# mySensorsRS485GW_back.net
KiCad netlist of a schematic drawn in EAGLE
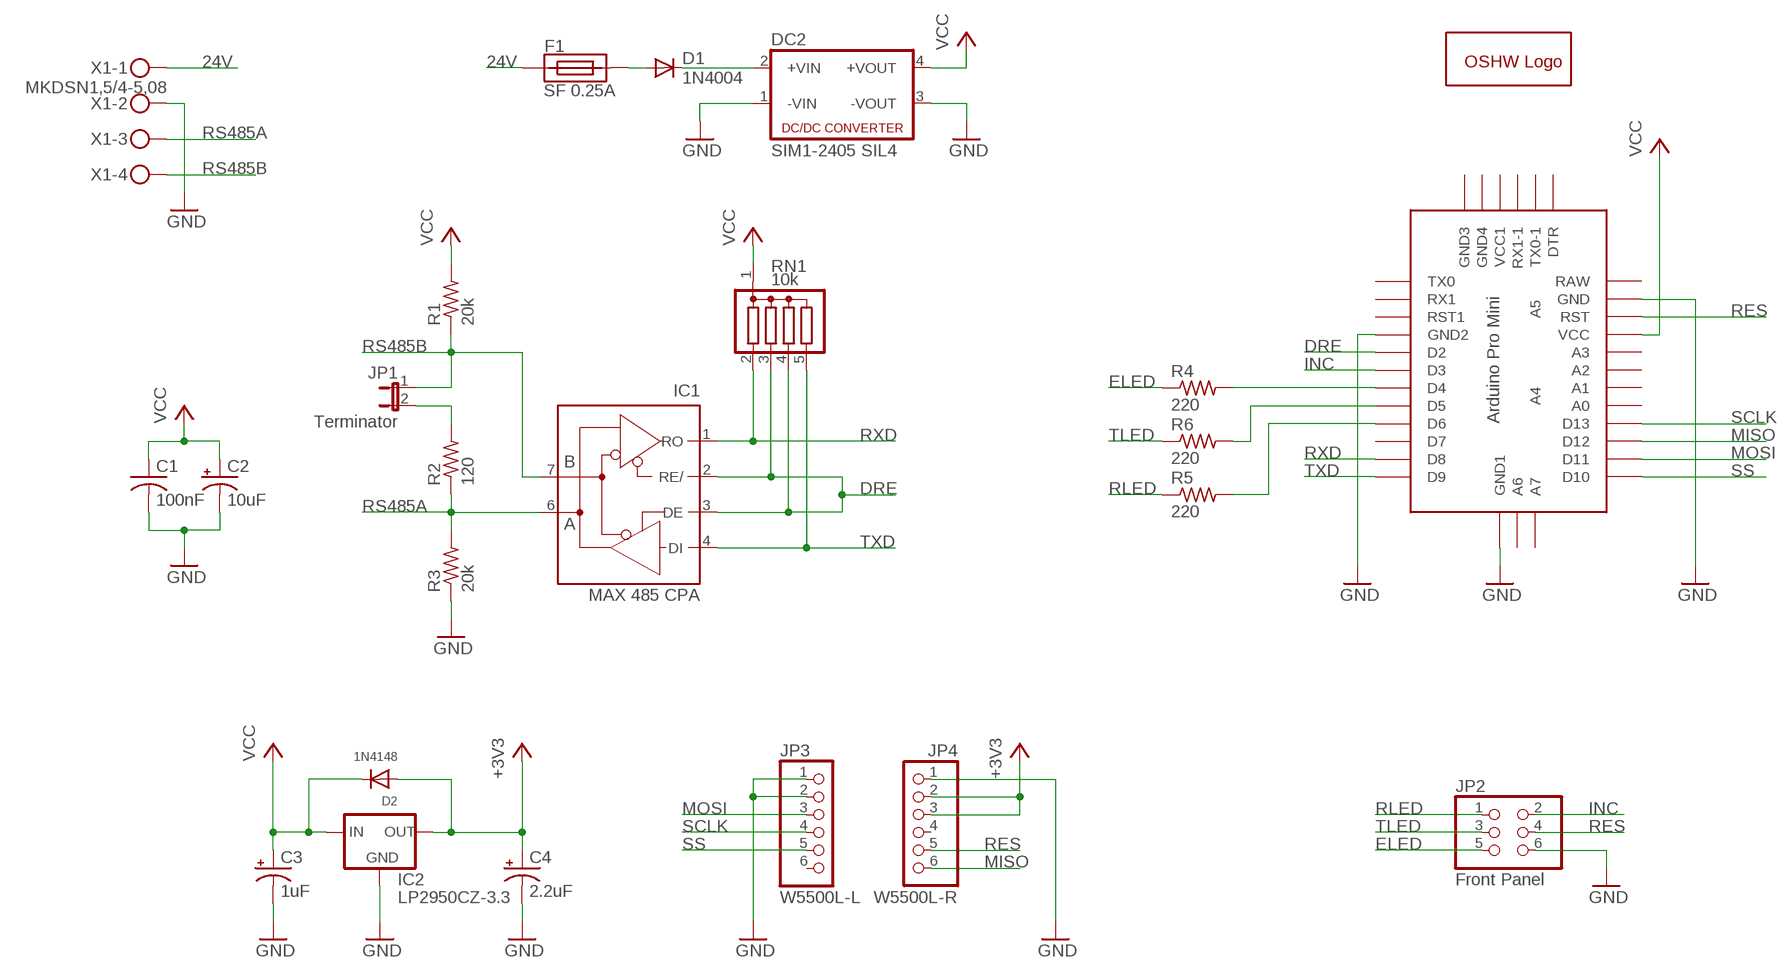
[diagram p0: schematic, sheet 1]

(export (version "E")
  (design (tool "Eeschema 10.0.6"))
  (components
    (comp (ref "C1")
      (value "100nF")
      (footprint "eagle-import:C025-025X050")
      (libsource (lib "eagle-import") (part "C-US025-025X050"))
    )
    (comp (ref "C2")
      (value "10uF")
      (footprint "eagle-import:TT2D5")
      (libsource (lib "eagle-import") (part "CPOL-USTT2D5"))
    )
    (comp (ref "C3")
      (value "1uF")
      (footprint "eagle-import:TT2D5")
      (libsource (lib "eagle-import") (part "CPOL-USTT2D5"))
    )
    (comp (ref "C4")
      (value "2.2uF")
      (footprint "eagle-import:TT2D5")
      (libsource (lib "eagle-import") (part "CPOL-USTT2D5"))
    )
    (comp (ref "D1")
      (value "1N4004")
      (footprint "eagle-import:DO41-10")
      (libsource (lib "eagle-import") (part "1N4004"))
    )
    (comp (ref "D2")
      (value "1N4148")
      (footprint "eagle-import:DO-1N4148")
      (libsource (lib "eagle-import") (part "DIODEDO-1N4148"))
    )
    (comp (ref "DC2")
      (value "SIM1-2405 SIL4")
      (footprint "eagle-import:NME")
      (fields (field (name "MF") "C & D TECHNOLOGIES, INC") (field (name "MPN") "NME1205D"))
      (libsource (lib "eagle-import") (part "NME"))
    )
    (comp (ref "F1")
      (value "SF 0.25A")
      (footprint "eagle-import:NANO2_SMF_FUSEBLOCK")
      (libsource (lib "eagle-import") (part "SMF_OMNIBLOK_154.062"))
    )
    (comp (ref "GOLD_ORB_SM1")
      (value "OSHWLOGOLOGO5MM")
      (footprint "eagle-import:OSHW_5MM")
      (libsource (lib "eagle-import") (part "OSHWLOGOLOGO5MM"))
    )
    (comp (ref "IC1")
      (value "MAX 485 CPA")
      (footprint "eagle-import:DIL08")
      (fields (field (name "MPN") "MAX481CPA+"))
      (libsource (lib "eagle-import") (part "MAX481CPA"))
    )
    (comp (ref "IC2")
      (value "LP2950CZ-3.3")
      (footprint "eagle-import:TO92")
      (libsource (lib "eagle-import") (part "LP2950?CZ-3.3"))
    )
    (comp (ref "JP1")
      (value "Terminator")
      (footprint "eagle-import:JP1")
      (libsource (lib "eagle-import") (part "JP1E"))
    )
    (comp (ref "JP2")
      (value "Front Panel")
      (footprint "eagle-import:2X03")
      (libsource (lib "eagle-import") (part "PINHD-2X3"))
    )
    (comp (ref "JP3")
      (value "W5500L-L")
      (footprint "eagle-import:1X06")
      (libsource (lib "eagle-import") (part "PINHD-1X6"))
    )
    (comp (ref "JP4")
      (value "W5500L-R")
      (footprint "eagle-import:1X06")
      (libsource (lib "eagle-import") (part "PINHD-1X6"))
    )
    (comp (ref "R1")
      (value "20k")
      (footprint "eagle-import:0207_2V")
      (libsource (lib "eagle-import") (part "R-US_0207/2V"))
    )
    (comp (ref "R2")
      (value "120")
      (footprint "eagle-import:0207_2V")
      (libsource (lib "eagle-import") (part "R-US_0207/2V"))
    )
    (comp (ref "R3")
      (value "20k")
      (footprint "eagle-import:0207_2V")
      (libsource (lib "eagle-import") (part "R-US_0207/2V"))
    )
    (comp (ref "R4")
      (value "220")
      (footprint "eagle-import:0207_7")
      (libsource (lib "eagle-import") (part "R-US_0207/7"))
    )
    (comp (ref "R5")
      (value "220")
      (footprint "eagle-import:0207_7")
      (libsource (lib "eagle-import") (part "R-US_0207/7"))
    )
    (comp (ref "R6")
      (value "220")
      (footprint "eagle-import:0207_7")
      (libsource (lib "eagle-import") (part "R-US_0207/7"))
    )
    (comp (ref "RN1")
      (value "10k")
      (footprint "eagle-import:SIL5")
      (libsource (lib "eagle-import") (part "G04R"))
    )
    (comp (ref "U$1")
      (value "ABK-PRO-MINI")
      (footprint "eagle-import:ABK-PRO-MINI")
      (libsource (lib "eagle-import") (part "ABK-PRO-MINI"))
    )
    (comp (ref "X1")
      (value "MKDSN1,5/4-5,08")
      (footprint "eagle-import:MKDSN1,5_4-5,08")
      (libsource (lib "eagle-import") (part "MKDSN1,5/4-5,08"))
    )
  )
  (nets
    (net (code "1") (name "+3V3") (class "Default")
      (node (ref "C4") (pin "+") (pinfunction "+_+") (pintype "passive"))
      (node (ref "D2") (pin "A") (pinfunction "A_A") (pintype "passive"))
      (node (ref "IC2") (pin "1") (pinfunction "OUT_1") (pintype "passive"))
      (node (ref "JP4") (pin "2") (pinfunction "2_2") (pintype "passive"))
      (node (ref "JP4") (pin "3") (pinfunction "3_3") (pintype "passive"))
    )
    (net (code "2") (name "/24V") (class "Default")
      (node (ref "F1") (pin "1") (pinfunction "1_1") (pintype "passive"))
      (node (ref "X1") (pin "1") (pinfunction "KL_1") (pintype "passive"))
    )
    (net (code "3") (name "/DRE") (class "Default")
      (node (ref "IC1") (pin "2") (pinfunction "RE/_2") (pintype "input"))
      (node (ref "IC1") (pin "3") (pinfunction "DE_3") (pintype "input"))
      (node (ref "RN1") (pin "3") (pinfunction "3_3") (pintype "passive"))
      (node (ref "RN1") (pin "4") (pinfunction "4_4") (pintype "passive"))
      (node (ref "U$1") (pin "D2") (pinfunction "D2_D2") (pintype "bidirectional"))
    )
    (net (code "4") (name "/ELED") (class "Default")
      (node (ref "JP2") (pin "5") (pinfunction "5_5") (pintype "passive"))
      (node (ref "R4") (pin "1") (pinfunction "1_1") (pintype "passive"))
    )
    (net (code "5") (name "/INC") (class "Default")
      (node (ref "JP2") (pin "2") (pinfunction "2_2") (pintype "passive"))
      (node (ref "U$1") (pin "D3") (pinfunction "D3_D3") (pintype "bidirectional"))
    )
    (net (code "6") (name "/MISO") (class "Default")
      (node (ref "JP4") (pin "6") (pinfunction "6_6") (pintype "passive"))
      (node (ref "U$1") (pin "D12") (pinfunction "D12_D12") (pintype "bidirectional"))
    )
    (net (code "7") (name "/MOSI") (class "Default")
      (node (ref "JP3") (pin "3") (pinfunction "3_3") (pintype "passive"))
      (node (ref "U$1") (pin "D11") (pinfunction "D11_D11") (pintype "bidirectional"))
    )
    (net (code "8") (name "/RES") (class "Default")
      (node (ref "JP2") (pin "4") (pinfunction "4_4") (pintype "passive"))
      (node (ref "JP4") (pin "5") (pinfunction "5_5") (pintype "passive"))
      (node (ref "U$1") (pin "RST") (pinfunction "RST_RST") (pintype "bidirectional"))
    )
    (net (code "9") (name "/RLED") (class "Default")
      (node (ref "JP2") (pin "1") (pinfunction "1_1") (pintype "passive"))
      (node (ref "R5") (pin "1") (pinfunction "1_1") (pintype "passive"))
    )
    (net (code "10") (name "/RS485A") (class "Default")
      (node (ref "IC1") (pin "6") (pinfunction "A_6") (pintype "passive"))
      (node (ref "R2") (pin "1") (pinfunction "1_1") (pintype "passive"))
      (node (ref "R3") (pin "2") (pinfunction "2_2") (pintype "passive"))
      (node (ref "X1") (pin "3") (pinfunction "KL_3") (pintype "passive"))
    )
    (net (code "11") (name "/RS485B") (class "Default")
      (node (ref "IC1") (pin "7") (pinfunction "B_7") (pintype "passive"))
      (node (ref "JP1") (pin "1") (pinfunction "1_1") (pintype "passive"))
      (node (ref "R1") (pin "1") (pinfunction "1_1") (pintype "passive"))
      (node (ref "X1") (pin "4") (pinfunction "KL_4") (pintype "passive"))
    )
    (net (code "12") (name "/RXD") (class "Default")
      (node (ref "IC1") (pin "1") (pinfunction "RO_1") (pintype "output"))
      (node (ref "RN1") (pin "2") (pinfunction "2_2") (pintype "passive"))
      (node (ref "U$1") (pin "D8") (pinfunction "D8_D8") (pintype "bidirectional"))
    )
    (net (code "13") (name "/SCLK") (class "Default")
      (node (ref "JP3") (pin "4") (pinfunction "4_4") (pintype "passive"))
      (node (ref "U$1") (pin "D13") (pinfunction "D13_D13") (pintype "bidirectional"))
    )
    (net (code "14") (name "/SS") (class "Default")
      (node (ref "JP3") (pin "5") (pinfunction "5_5") (pintype "passive"))
      (node (ref "U$1") (pin "D10") (pinfunction "D10_D10") (pintype "bidirectional"))
    )
    (net (code "15") (name "/TLED") (class "Default")
      (node (ref "JP2") (pin "3") (pinfunction "3_3") (pintype "passive"))
      (node (ref "R6") (pin "1") (pinfunction "1_1") (pintype "passive"))
    )
    (net (code "16") (name "/TXD") (class "Default")
      (node (ref "IC1") (pin "4") (pinfunction "DI_4") (pintype "input"))
      (node (ref "RN1") (pin "5") (pinfunction "5_5") (pintype "passive"))
      (node (ref "U$1") (pin "D9") (pinfunction "D9_D9") (pintype "bidirectional"))
    )
    (net (code "17") (name "GND") (class "Default")
      (node (ref "C1") (pin "2") (pinfunction "2_2") (pintype "passive"))
      (node (ref "C2") (pin "-") (pinfunction "-_-") (pintype "passive"))
      (node (ref "C3") (pin "-") (pinfunction "-_-") (pintype "passive"))
      (node (ref "C4") (pin "-") (pinfunction "-_-") (pintype "passive"))
      (node (ref "DC2") (pin "1") (pinfunction "-VIN_1") (pintype "passive"))
      (node (ref "DC2") (pin "3") (pinfunction "-VOUT_3") (pintype "passive"))
      (node (ref "IC2") (pin "2") (pinfunction "GND_2") (pintype "input"))
      (node (ref "JP2") (pin "6") (pinfunction "6_6") (pintype "passive"))
      (node (ref "JP3") (pin "1") (pinfunction "1_1") (pintype "passive"))
      (node (ref "JP3") (pin "2") (pinfunction "2_2") (pintype "passive"))
      (node (ref "JP4") (pin "1") (pinfunction "1_1") (pintype "passive"))
      (node (ref "R3") (pin "1") (pinfunction "1_1") (pintype "passive"))
      (node (ref "U$1") (pin "GND") (pinfunction "GND_GND") (pintype "bidirectional"))
      (node (ref "U$1") (pin "GND1") (pinfunction "GND2_GND1") (pintype "bidirectional"))
      (node (ref "U$1") (pin "GND4") (pinfunction "GND1_GND4") (pintype "bidirectional"))
      (node (ref "X1") (pin "2") (pinfunction "KL_2") (pintype "passive"))
    )
    (net (code "18") (name "Net-(D1-PadA)") (class "Default")
      (node (ref "D1") (pin "A") (pinfunction "A_A") (pintype "passive"))
      (node (ref "F1") (pin "2") (pinfunction "2_2") (pintype "passive"))
    )
    (net (code "19") (name "Net-(DC2-+VIN)") (class "Default")
      (node (ref "D1") (pin "C") (pinfunction "C_C") (pintype "passive"))
      (node (ref "DC2") (pin "2") (pinfunction "+VIN_2") (pintype "passive"))
    )
    (net (code "20") (name "Net-(JP1-Pad2)") (class "Default")
      (node (ref "JP1") (pin "2") (pinfunction "2_2") (pintype "passive"))
      (node (ref "R2") (pin "2") (pinfunction "2_2") (pintype "passive"))
    )
    (net (code "21") (name "Net-(R4-Pad2)") (class "Default")
      (node (ref "R4") (pin "2") (pinfunction "2_2") (pintype "passive"))
      (node (ref "U$1") (pin "D4") (pinfunction "D4_D4") (pintype "bidirectional"))
    )
    (net (code "22") (name "Net-(R5-Pad2)") (class "Default")
      (node (ref "R5") (pin "2") (pinfunction "2_2") (pintype "passive"))
      (node (ref "U$1") (pin "D6") (pinfunction "D6_D6") (pintype "bidirectional"))
    )
    (net (code "23") (name "Net-(R6-Pad2)") (class "Default")
      (node (ref "R6") (pin "2") (pinfunction "2_2") (pintype "passive"))
      (node (ref "U$1") (pin "D5") (pinfunction "D5_D5") (pintype "bidirectional"))
    )
    (net (code "24") (name "VCC") (class "Default")
      (node (ref "C1") (pin "1") (pinfunction "1_1") (pintype "passive"))
      (node (ref "C2") (pin "+") (pinfunction "+_+") (pintype "passive"))
      (node (ref "C3") (pin "+") (pinfunction "+_+") (pintype "passive"))
      (node (ref "D2") (pin "C") (pinfunction "C_C") (pintype "passive"))
      (node (ref "DC2") (pin "4") (pinfunction "+VOUT_4") (pintype "passive"))
      (node (ref "IC2") (pin "3") (pinfunction "IN_3") (pintype "input"))
      (node (ref "R1") (pin "2") (pinfunction "2_2") (pintype "passive"))
      (node (ref "RN1") (pin "1") (pinfunction "1_1") (pintype "passive"))
      (node (ref "U$1") (pin "VCC") (pinfunction "VCC_VCC") (pintype "bidirectional"))
    )
    (net (code "25") (name "unconnected-(JP3-Pad6)") (class "Default")
      (node (ref "JP3") (pin "6") (pinfunction "6_6") (pintype "passive"))
    )
    (net (code "26") (name "unconnected-(JP4-Pad4)") (class "Default")
      (node (ref "JP4") (pin "4") (pinfunction "4_4") (pintype "passive"))
    )
    (net (code "27") (name "unconnected-(U$1-GND3-PadGND2)") (class "Default")
      (node (ref "U$1") (pin "GND2") (pinfunction "GND3_GND2") (pintype "bidirectional"))
    )
    (net (code "28") (name "unconnected-(U$1-GND4-PadGND3)") (class "Default")
      (node (ref "U$1") (pin "GND3") (pinfunction "GND4_GND3") (pintype "bidirectional"))
    )
    (net (code "29") (name "unconnected-(U$1-PadA0)") (class "Default")
      (node (ref "U$1") (pin "A0") (pinfunction "A0_A0") (pintype "bidirectional"))
    )
    (net (code "30") (name "unconnected-(U$1-PadA1)") (class "Default")
      (node (ref "U$1") (pin "A1") (pinfunction "A1_A1") (pintype "bidirectional"))
    )
    (net (code "31") (name "unconnected-(U$1-PadA2)") (class "Default")
      (node (ref "U$1") (pin "A2") (pinfunction "A2_A2") (pintype "bidirectional"))
    )
    (net (code "32") (name "unconnected-(U$1-PadA3)") (class "Default")
      (node (ref "U$1") (pin "A3") (pinfunction "A3_A3") (pintype "bidirectional"))
    )
    (net (code "33") (name "unconnected-(U$1-PadA4)") (class "Default")
      (node (ref "U$1") (pin "A4") (pinfunction "A4_A4") (pintype "bidirectional"))
    )
    (net (code "34") (name "unconnected-(U$1-PadA5)") (class "Default")
      (node (ref "U$1") (pin "A5") (pinfunction "A5_A5") (pintype "bidirectional"))
    )
    (net (code "35") (name "unconnected-(U$1-PadA6)") (class "Default")
      (node (ref "U$1") (pin "A6") (pinfunction "A6_A6") (pintype "bidirectional"))
    )
    (net (code "36") (name "unconnected-(U$1-PadA7)") (class "Default")
      (node (ref "U$1") (pin "A7") (pinfunction "A7_A7") (pintype "bidirectional"))
    )
    (net (code "37") (name "unconnected-(U$1-PadD7)") (class "Default")
      (node (ref "U$1") (pin "D7") (pinfunction "D7_D7") (pintype "bidirectional"))
    )
    (net (code "38") (name "unconnected-(U$1-PadDTR)") (class "Default")
      (node (ref "U$1") (pin "DTR") (pinfunction "DTR_DTR") (pintype "bidirectional"))
    )
    (net (code "39") (name "unconnected-(U$1-PadRAW)") (class "Default")
      (node (ref "U$1") (pin "RAW") (pinfunction "RAW_RAW") (pintype "bidirectional"))
    )
    (net (code "40") (name "unconnected-(U$1-PadRST1)") (class "Default")
      (node (ref "U$1") (pin "RST1") (pinfunction "RST1_RST1") (pintype "bidirectional"))
    )
    (net (code "41") (name "unconnected-(U$1-PadRX1)") (class "Default")
      (node (ref "U$1") (pin "RX1") (pinfunction "RX1_RX1") (pintype "bidirectional"))
    )
    (net (code "42") (name "unconnected-(U$1-PadRX1-1)") (class "Default")
      (node (ref "U$1") (pin "RX1-1") (pinfunction "RX1-1_RX1-1") (pintype "bidirectional"))
    )
    (net (code "43") (name "unconnected-(U$1-PadTX0)") (class "Default")
      (node (ref "U$1") (pin "TX0") (pinfunction "TX0_TX0") (pintype "bidirectional"))
    )
    (net (code "44") (name "unconnected-(U$1-PadTX0-1)") (class "Default")
      (node (ref "U$1") (pin "TX0-1") (pinfunction "TX0-1_TX0-1") (pintype "bidirectional"))
    )
    (net (code "45") (name "unconnected-(U$1-PadVCC1)") (class "Default")
      (node (ref "U$1") (pin "VCC1") (pinfunction "VCC1_VCC1") (pintype "bidirectional"))
    )
  )
)
